# Buck_PM.net
KiCad netlist of a schematic drawn in Altium Designer
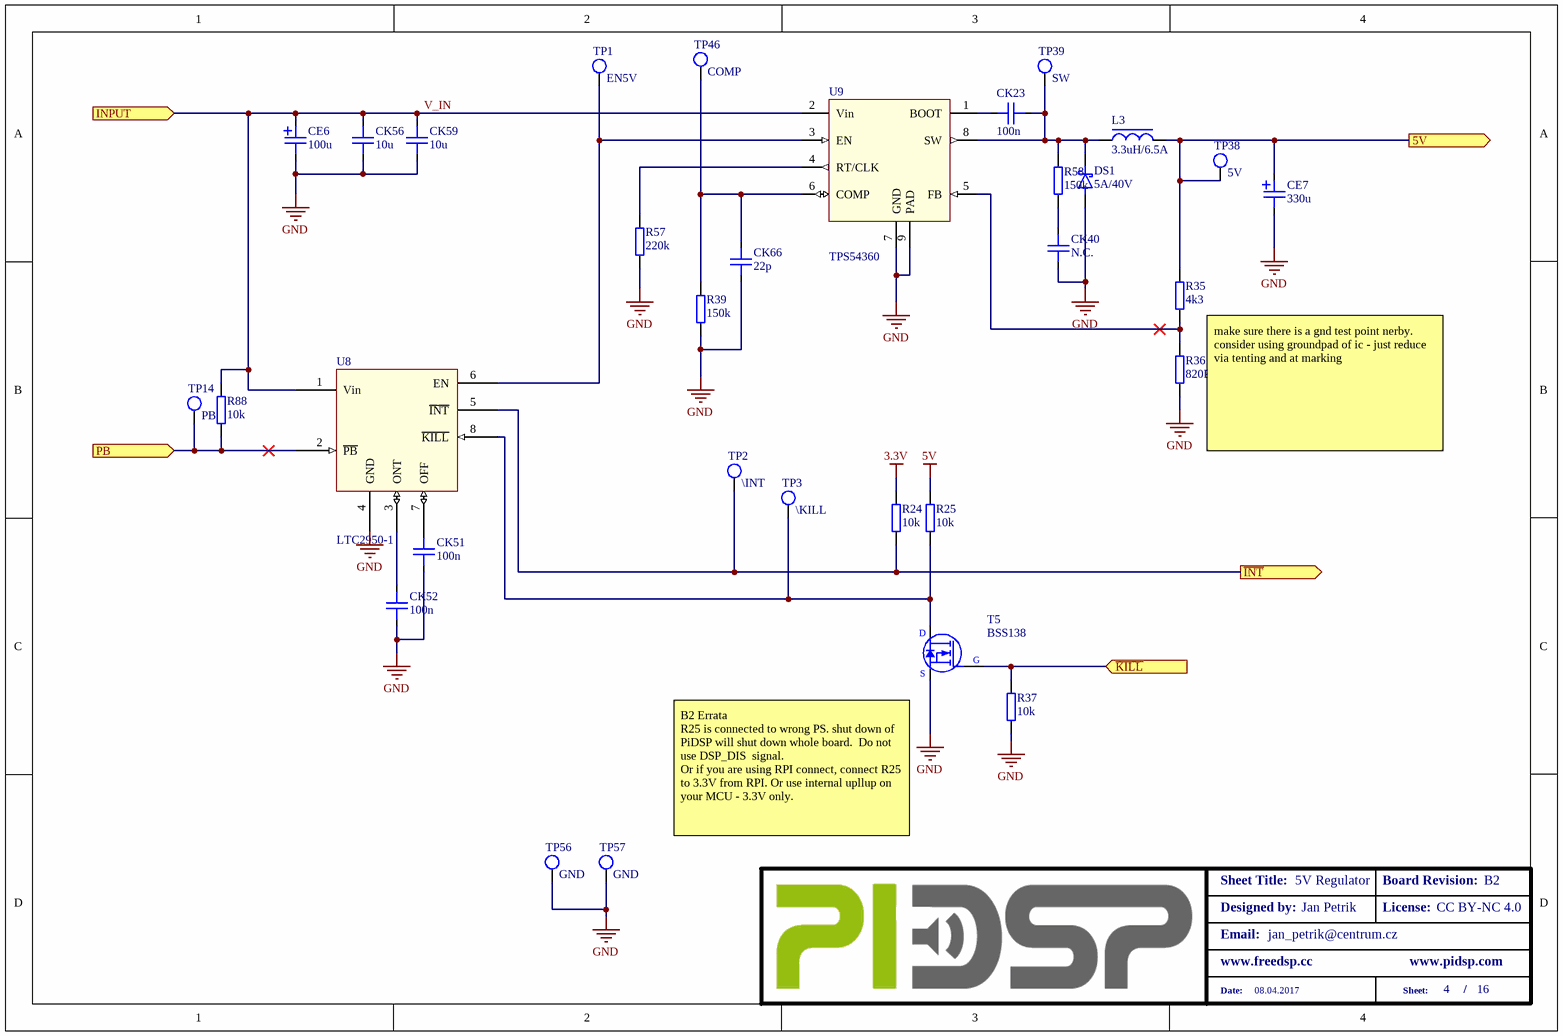
[diagram p0: Buck+PM.SchDoc]

(export (version "E")
  (design (tool "Eeschema 10.0.6"))
  (components
    (comp (ref "CE6")
      (value "100u")
      (footprint "CAPAE6.8X6.8(D_SIZE)")
      (description "Polymer Aluminium Solid Capacitor 100uF, 16V")
      (fields
        (field (name "TOLERANCE") "20%/16V")
        (field (name "VOLTAGE") "16V")
        (field (name "AUTHOR") "JP/27.03.2014")
      )
      (libsource (lib "JP_C") (part "100u-16V-B6-OSCON"))
    )
    (comp (ref "CE7")
      (value "330u")
      (footprint "CAPAE6.8X6.8(D_SIZE)")
      (description "Polymer Aluminium Solid Capacitor 330uF, 6.3V")
      (fields
        (field (name "TOLERANCE") "20%/35V")
        (field (name "VOLTAGE") "6.3V")
        (field (name "AUTHOR") "JP/27.03.2014")
      )
      (libsource (lib "JP_C") (part "330u-6.3V-B6-OSCON"))
    )
    (comp (ref "CK23")
      (value "100n")
      (footprint "CAPC1608X09N(SMC0603)")
      (description "MLCC")
      (fields
        (field (name "VOLTAGE") "50V")
        (field (name "TOLERANCE") "10%")
        (field (name "AUTHOR") "JP/27.03.2014")
      )
      (libsource (lib "JP_C") (part "100n-50V-0603-X7R"))
    )
    (comp (ref "CK40")
      (value "N.C.")
      (footprint "CAPC1608X09N(SMC0603)")
      (description "MLCC")
      (fields
        (field (name "VOLTAGE") "50V")
        (field (name "TOLERANCE") "10%")
        (field (name "AUTHOR") "JP/27.03.2014")
      )
      (libsource (lib "JP_C") (part "100n-50V-0603-X7R"))
    )
    (comp (ref "CK51")
      (value "100n")
      (footprint "CAPC1608X09N(SMC0603)")
      (description "MLCC")
      (fields
        (field (name "VOLTAGE") "50V")
        (field (name "TOLERANCE") "10%")
        (field (name "AUTHOR") "JP/27.03.2014")
      )
      (libsource (lib "JP_C") (part "100n-50V-0603-X7R"))
    )
    (comp (ref "CK52")
      (value "100n")
      (footprint "CAPC1608X09N(SMC0603)")
      (description "MLCC")
      (fields
        (field (name "VOLTAGE") "50V")
        (field (name "TOLERANCE") "10%")
        (field (name "AUTHOR") "JP/27.03.2014")
      )
      (libsource (lib "JP_C") (part "100n-50V-0603-X7R"))
    )
    (comp (ref "CK56")
      (value "10u")
      (footprint "CAPC3216X12N(SMC1206)")
      (description "MLCC")
      (fields
        (field (name "VOLTAGE") "50")
        (field (name "TOLERANCE") "10%")
        (field (name "AUTHOR") "JP/10.06.2014")
      )
      (libsource (lib "JP_C") (part "10u-50V-1206-X5R"))
    )
    (comp (ref "CK59")
      (value "10u")
      (footprint "CAPC3216X12N(SMC1206)")
      (description "MLCC")
      (fields
        (field (name "VOLTAGE") "50")
        (field (name "TOLERANCE") "10%")
        (field (name "AUTHOR") "JP/10.06.2014")
      )
      (libsource (lib "JP_C") (part "10u-50V-1206-X5R"))
    )
    (comp (ref "CK66")
      (value "22p")
      (footprint "CAPC1608X09N(SMC0603)")
      (description "MLCC")
      (fields
        (field (name "TOLERANCE") "10%")
        (field (name "VOLTAGE") "50V")
        (field (name "AUTHOR") "JP/27.03.2014")
      )
      (libsource (lib "JP_C") (part "22p-50V-0603-NP0"))
    )
    (comp (ref "DS1")
      (value "5A/40V")
      (footprint "DIOM6959X26M(SMC)")
      (description "High Current Density SMT Schottky Rectifier, 5A/40V, SMC")
      (libsource (lib "JP_IC") (part "SSC54-E3"))
    )
    (comp (ref "L3")
      (value "3.3uH/6.5A")
      (footprint "INDM_7.2x6.5")
      (description "SRP6540 Series - Shielded Power Inductors")
      (libsource (lib "JP_L") (part "SRP6540_3.3u"))
    )
    (comp (ref "R24")
      (value "10k")
      (footprint "RESC1608X06N(SMR0603)")
      (description "Chip Resistor")
      (fields (field (name "AUTHOR") "JP/10.06.2014"))
      (libsource (lib "JP_R") (part "10k-100mW-0603-ThickFilm"))
    )
    (comp (ref "R25")
      (value "10k")
      (footprint "RESC1608X06N(SMR0603)")
      (description "Chip Resistor")
      (fields (field (name "AUTHOR") "JP/10.06.2014"))
      (libsource (lib "JP_R") (part "10k-100mW-0603-ThickFilm"))
    )
    (comp (ref "R35")
      (value "4k3")
      (footprint "RESC1608X06N(SMR0603)")
      (description "Chip Resistor")
      (fields (field (name "AUTHOR") "JP/10.06.2014"))
      (libsource (lib "JP_R") (part "4K3-100mW-0603-ThickFilm"))
    )
    (comp (ref "R36")
      (value "820R")
      (footprint "RESC1608X06N(SMR0603)")
      (description "Chip Resistor")
      (fields (field (name "AUTHOR") "JP/10.06.2014"))
      (libsource (lib "JP_R") (part "820R-100mW-0603-ThickFilm"))
    )
    (comp (ref "R37")
      (value "10k")
      (footprint "RESC1608X06N(SMR0603)")
      (description "Chip Resistor")
      (fields (field (name "AUTHOR") "JP/10.06.2014"))
      (libsource (lib "JP_R") (part "10k-100mW-0603-ThickFilm"))
    )
    (comp (ref "R39")
      (value "150k")
      (footprint "RESC1608X06N(SMR0603)")
      (description "Chip Resistor")
      (fields (field (name "AUTHOR") "JP/10.06.2014"))
      (libsource (lib "JP_R") (part "150k-100mW-0603-ThickFilm"))
    )
    (comp (ref "R57")
      (value "220k")
      (footprint "RESC1608X06N(SMR0603)")
      (description "Chip Resistor")
      (fields (field (name "AUTHOR") "JP/10.06.2014"))
      (libsource (lib "JP_R") (part "220k-100mW-0603-ThickFilm"))
    )
    (comp (ref "R58")
      (value "150k")
      (footprint "RESC1608X06N(SMR0603)")
      (description "Chip Resistor")
      (fields (field (name "AUTHOR") "JP/10.06.2014"))
      (libsource (lib "JP_R") (part "150k-100mW-0603-ThickFilm"))
    )
    (comp (ref "R88")
      (value "10k")
      (footprint "RESC1608X06N(SMR0603)")
      (description "Chip Resistor")
      (fields (field (name "AUTHOR") "JP/10.06.2014"))
      (libsource (lib "JP_R") (part "10k-100mW-0603-ThickFilm"))
    )
    (comp (ref "T5")
      (value "BSS138")
      (footprint "SOT95P230X110-3N(SOT23)")
      (description "N-MOSFET, Logic Level, 50V/0,22A/3.5Ohm")
      (fields (field (name "AUTHOR") "JM 2.7.2014"))
      (libsource (lib "JP_IC") (part "ET+BSS138XX0"))
    )
    (comp (ref "TP1")
      (value "EN5V")
      (footprint "TP_0.8/0.4_ROUND")
      (description "Testpoint - VIA")
      (libsource (lib "JP_CONN") (part "TEST_POINT_VIA"))
    )
    (comp (ref "TP2")
      (value "INT")
      (footprint "TP_0.8/0.4_ROUND")
      (description "Testpoint - VIA")
      (libsource (lib "JP_CONN") (part "TEST_POINT_VIA"))
    )
    (comp (ref "TP3")
      (value "KILL")
      (footprint "TP_0.8/0.4_ROUND")
      (description "Testpoint - VIA")
      (libsource (lib "JP_CONN") (part "TEST_POINT_VIA"))
    )
    (comp (ref "TP14")
      (value "PB")
      (footprint "TP_0.8/0.4_ROUND")
      (description "Testpoint - VIA")
      (libsource (lib "JP_CONN") (part "TEST_POINT_VIA"))
    )
    (comp (ref "TP38")
      (value "5V")
      (footprint "TP_0.8/0.4_ROUND")
      (description "Testpoint - VIA")
      (libsource (lib "JP_CONN") (part "TEST_POINT_VIA"))
    )
    (comp (ref "TP39")
      (value "SW")
      (footprint "TP_0.8/0.4_ROUND")
      (description "Testpoint - VIA")
      (libsource (lib "JP_CONN") (part "TEST_POINT_VIA"))
    )
    (comp (ref "TP46")
      (value "COMP")
      (footprint "TP_0.8/0.4_ROUND")
      (description "Testpoint - VIA")
      (libsource (lib "JP_CONN") (part "TEST_POINT_VIA"))
    )
    (comp (ref "TP56")
      (value "GND")
      (footprint "TP_0.8/0.4_ROUND")
      (description "Testpoint - VIA")
      (libsource (lib "JP_CONN") (part "TEST_POINT_VIA"))
    )
    (comp (ref "TP57")
      (value "GND")
      (footprint "TP_0.8/0.4_ROUND")
      (description "Testpoint - VIA")
      (libsource (lib "JP_CONN") (part "TEST_POINT_VIA"))
    )
    (comp (ref "U8")
      (value "LTC2950-1")
      (footprint "LT-TS8-8-TSOT-23_V")
      (description "Pushbutton On/Off    Controller")
      (libsource (lib "JP_IC") (part "LTC2950-1"))
    )
    (comp (ref "U9")
      (value "TPS54360")
      (footprint "SOIC127P600X175-8N(SOIC_8)-POWERPAD_HP")
      (description "3.5 A, Step Down DC-DC Converter")
      (libsource (lib "JP_IC") (part "TPS54360"))
    )
  )
  (nets
    (net (code "1") (name "/PB") (class "Default")
      (node (ref "R88") (pin "1") (pinfunction "1_1") (pintype "passive"))
      (node (ref "TP14") (pin "1") (pintype "passive"))
      (node (ref "U8") (pin "2") (pinfunction "~{PB}_2") (pintype "input"))
    )
    (net (code "2") (name "/V_IN") (class "Default")
      (node (ref "CE6") (pin "1") (pinfunction "1_1") (pintype "passive"))
      (node (ref "CK56") (pin "1") (pinfunction "1_1") (pintype "passive"))
      (node (ref "CK59") (pin "1") (pinfunction "1_1") (pintype "passive"))
      (node (ref "R88") (pin "2") (pinfunction "2_2") (pintype "passive"))
      (node (ref "U8") (pin "1") (pinfunction "Vin_1") (pintype "power_in"))
      (node (ref "U9") (pin "2") (pinfunction "Vin_2") (pintype "power_in"))
    )
    (net (code "3") (name "/~{INT}") (class "Default")
      (node (ref "R24") (pin "1") (pinfunction "1_1") (pintype "passive"))
      (node (ref "TP2") (pin "1") (pintype "passive"))
      (node (ref "U8") (pin "5") (pinfunction "~{INT}_5") (pintype "open_collector"))
    )
    (net (code "4") (name "/~{KILL}") (class "Default")
      (node (ref "R37") (pin "2") (pinfunction "2_2") (pintype "passive"))
      (node (ref "T5") (pin "1") (pinfunction "G_1") (pintype "passive"))
    )
    (net (code "5") (name "3.3V") (class "Default")
      (node (ref "R24") (pin "2") (pinfunction "2_2") (pintype "passive"))
    )
    (net (code "6") (name "5V") (class "Default")
      (node (ref "CE7") (pin "1") (pinfunction "1_1") (pintype "passive"))
      (node (ref "L3") (pin "2") (pintype "passive"))
      (node (ref "R25") (pin "2") (pinfunction "2_2") (pintype "passive"))
      (node (ref "R35") (pin "2") (pinfunction "2_2") (pintype "passive"))
      (node (ref "TP38") (pin "1") (pintype "passive"))
    )
    (net (code "7") (name "GND") (class "Default")
      (node (ref "CE6") (pin "2") (pinfunction "2_2") (pintype "passive"))
      (node (ref "CE7") (pin "2") (pinfunction "2_2") (pintype "passive"))
      (node (ref "CK40") (pin "2") (pinfunction "2_2") (pintype "passive"))
      (node (ref "CK51") (pin "2") (pinfunction "2_2") (pintype "passive"))
      (node (ref "CK52") (pin "2") (pinfunction "2_2") (pintype "passive"))
      (node (ref "CK56") (pin "2") (pinfunction "2_2") (pintype "passive"))
      (node (ref "CK59") (pin "2") (pinfunction "2_2") (pintype "passive"))
      (node (ref "CK66") (pin "1") (pinfunction "1_1") (pintype "passive"))
      (node (ref "DS1") (pin "2") (pinfunction "A_2") (pintype "passive"))
      (node (ref "R36") (pin "1") (pinfunction "1_1") (pintype "passive"))
      (node (ref "R37") (pin "1") (pinfunction "1_1") (pintype "passive"))
      (node (ref "R39") (pin "1") (pinfunction "1_1") (pintype "passive"))
      (node (ref "R57") (pin "1") (pinfunction "1_1") (pintype "passive"))
      (node (ref "T5") (pin "2") (pinfunction "S_2") (pintype "passive"))
      (node (ref "TP56") (pin "1") (pintype "passive"))
      (node (ref "TP57") (pin "1") (pintype "passive"))
      (node (ref "U8") (pin "4") (pinfunction "GND_4") (pintype "power_in"))
      (node (ref "U9") (pin "7") (pinfunction "GND_7") (pintype "power_in"))
      (node (ref "U9") (pin "9") (pinfunction "PAD_9") (pintype "power_in"))
    )
    (net (code "8") (name "Net-(CK40-Pad1)") (class "Default")
      (node (ref "CK40") (pin "1") (pinfunction "1_1") (pintype "passive"))
      (node (ref "R58") (pin "1") (pinfunction "1_1") (pintype "passive"))
    )
    (net (code "9") (name "Net-(DS1-C)") (class "Default")
      (node (ref "CK23") (pin "1") (pinfunction "1_1") (pintype "passive"))
      (node (ref "DS1") (pin "1") (pinfunction "C_1") (pintype "passive"))
      (node (ref "L3") (pin "1") (pintype "passive"))
      (node (ref "R58") (pin "2") (pinfunction "2_2") (pintype "passive"))
      (node (ref "TP39") (pin "1") (pintype "passive"))
      (node (ref "U9") (pin "8") (pinfunction "SW_8") (pintype "output"))
    )
    (net (code "10") (name "Net-(T5-D)") (class "Default")
      (node (ref "R25") (pin "1") (pinfunction "1_1") (pintype "passive"))
      (node (ref "T5") (pin "3") (pinfunction "D_3") (pintype "passive"))
      (node (ref "TP3") (pin "1") (pintype "passive"))
      (node (ref "U8") (pin "8") (pinfunction "~{KILL}_8") (pintype "input"))
    )
    (net (code "11") (name "Net-(U8-EN)") (class "Default")
      (node (ref "TP1") (pin "1") (pintype "passive"))
      (node (ref "U8") (pin "6") (pinfunction "EN_6") (pintype "open_collector"))
      (node (ref "U9") (pin "3") (pinfunction "EN_3") (pintype "input"))
    )
    (net (code "12") (name "Net-(U8-OFF)") (class "Default")
      (node (ref "CK51") (pin "1") (pinfunction "1_1") (pintype "passive"))
      (node (ref "U8") (pin "7") (pinfunction "OFF_7") (pintype "bidirectional"))
    )
    (net (code "13") (name "Net-(U8-ONT)") (class "Default")
      (node (ref "CK52") (pin "1") (pinfunction "1_1") (pintype "passive"))
      (node (ref "U8") (pin "3") (pinfunction "ONT_3") (pintype "bidirectional"))
    )
    (net (code "14") (name "Net-(U9-BOOT)") (class "Default")
      (node (ref "CK23") (pin "2") (pinfunction "2_2") (pintype "passive"))
      (node (ref "U9") (pin "1") (pinfunction "BOOT_1") (pintype "power_in"))
    )
    (net (code "15") (name "Net-(U9-COMP)") (class "Default")
      (node (ref "CK66") (pin "2") (pinfunction "2_2") (pintype "passive"))
      (node (ref "R39") (pin "2") (pinfunction "2_2") (pintype "passive"))
      (node (ref "TP46") (pin "1") (pintype "passive"))
      (node (ref "U9") (pin "6") (pinfunction "COMP_6") (pintype "bidirectional"))
    )
    (net (code "16") (name "Net-(U9-FB)") (class "Default")
      (node (ref "R35") (pin "1") (pinfunction "1_1") (pintype "passive"))
      (node (ref "R36") (pin "2") (pinfunction "2_2") (pintype "passive"))
      (node (ref "U9") (pin "5") (pinfunction "FB_5") (pintype "input"))
    )
    (net (code "17") (name "Net-(U9-RT{slash}CLK)") (class "Default")
      (node (ref "R57") (pin "2") (pinfunction "2_2") (pintype "passive"))
      (node (ref "U9") (pin "4") (pinfunction "RT/CLK_4") (pintype "output"))
    )
  )
)
